# Sheet1.net
KiCad netlist of a schematic drawn in Altium Designer
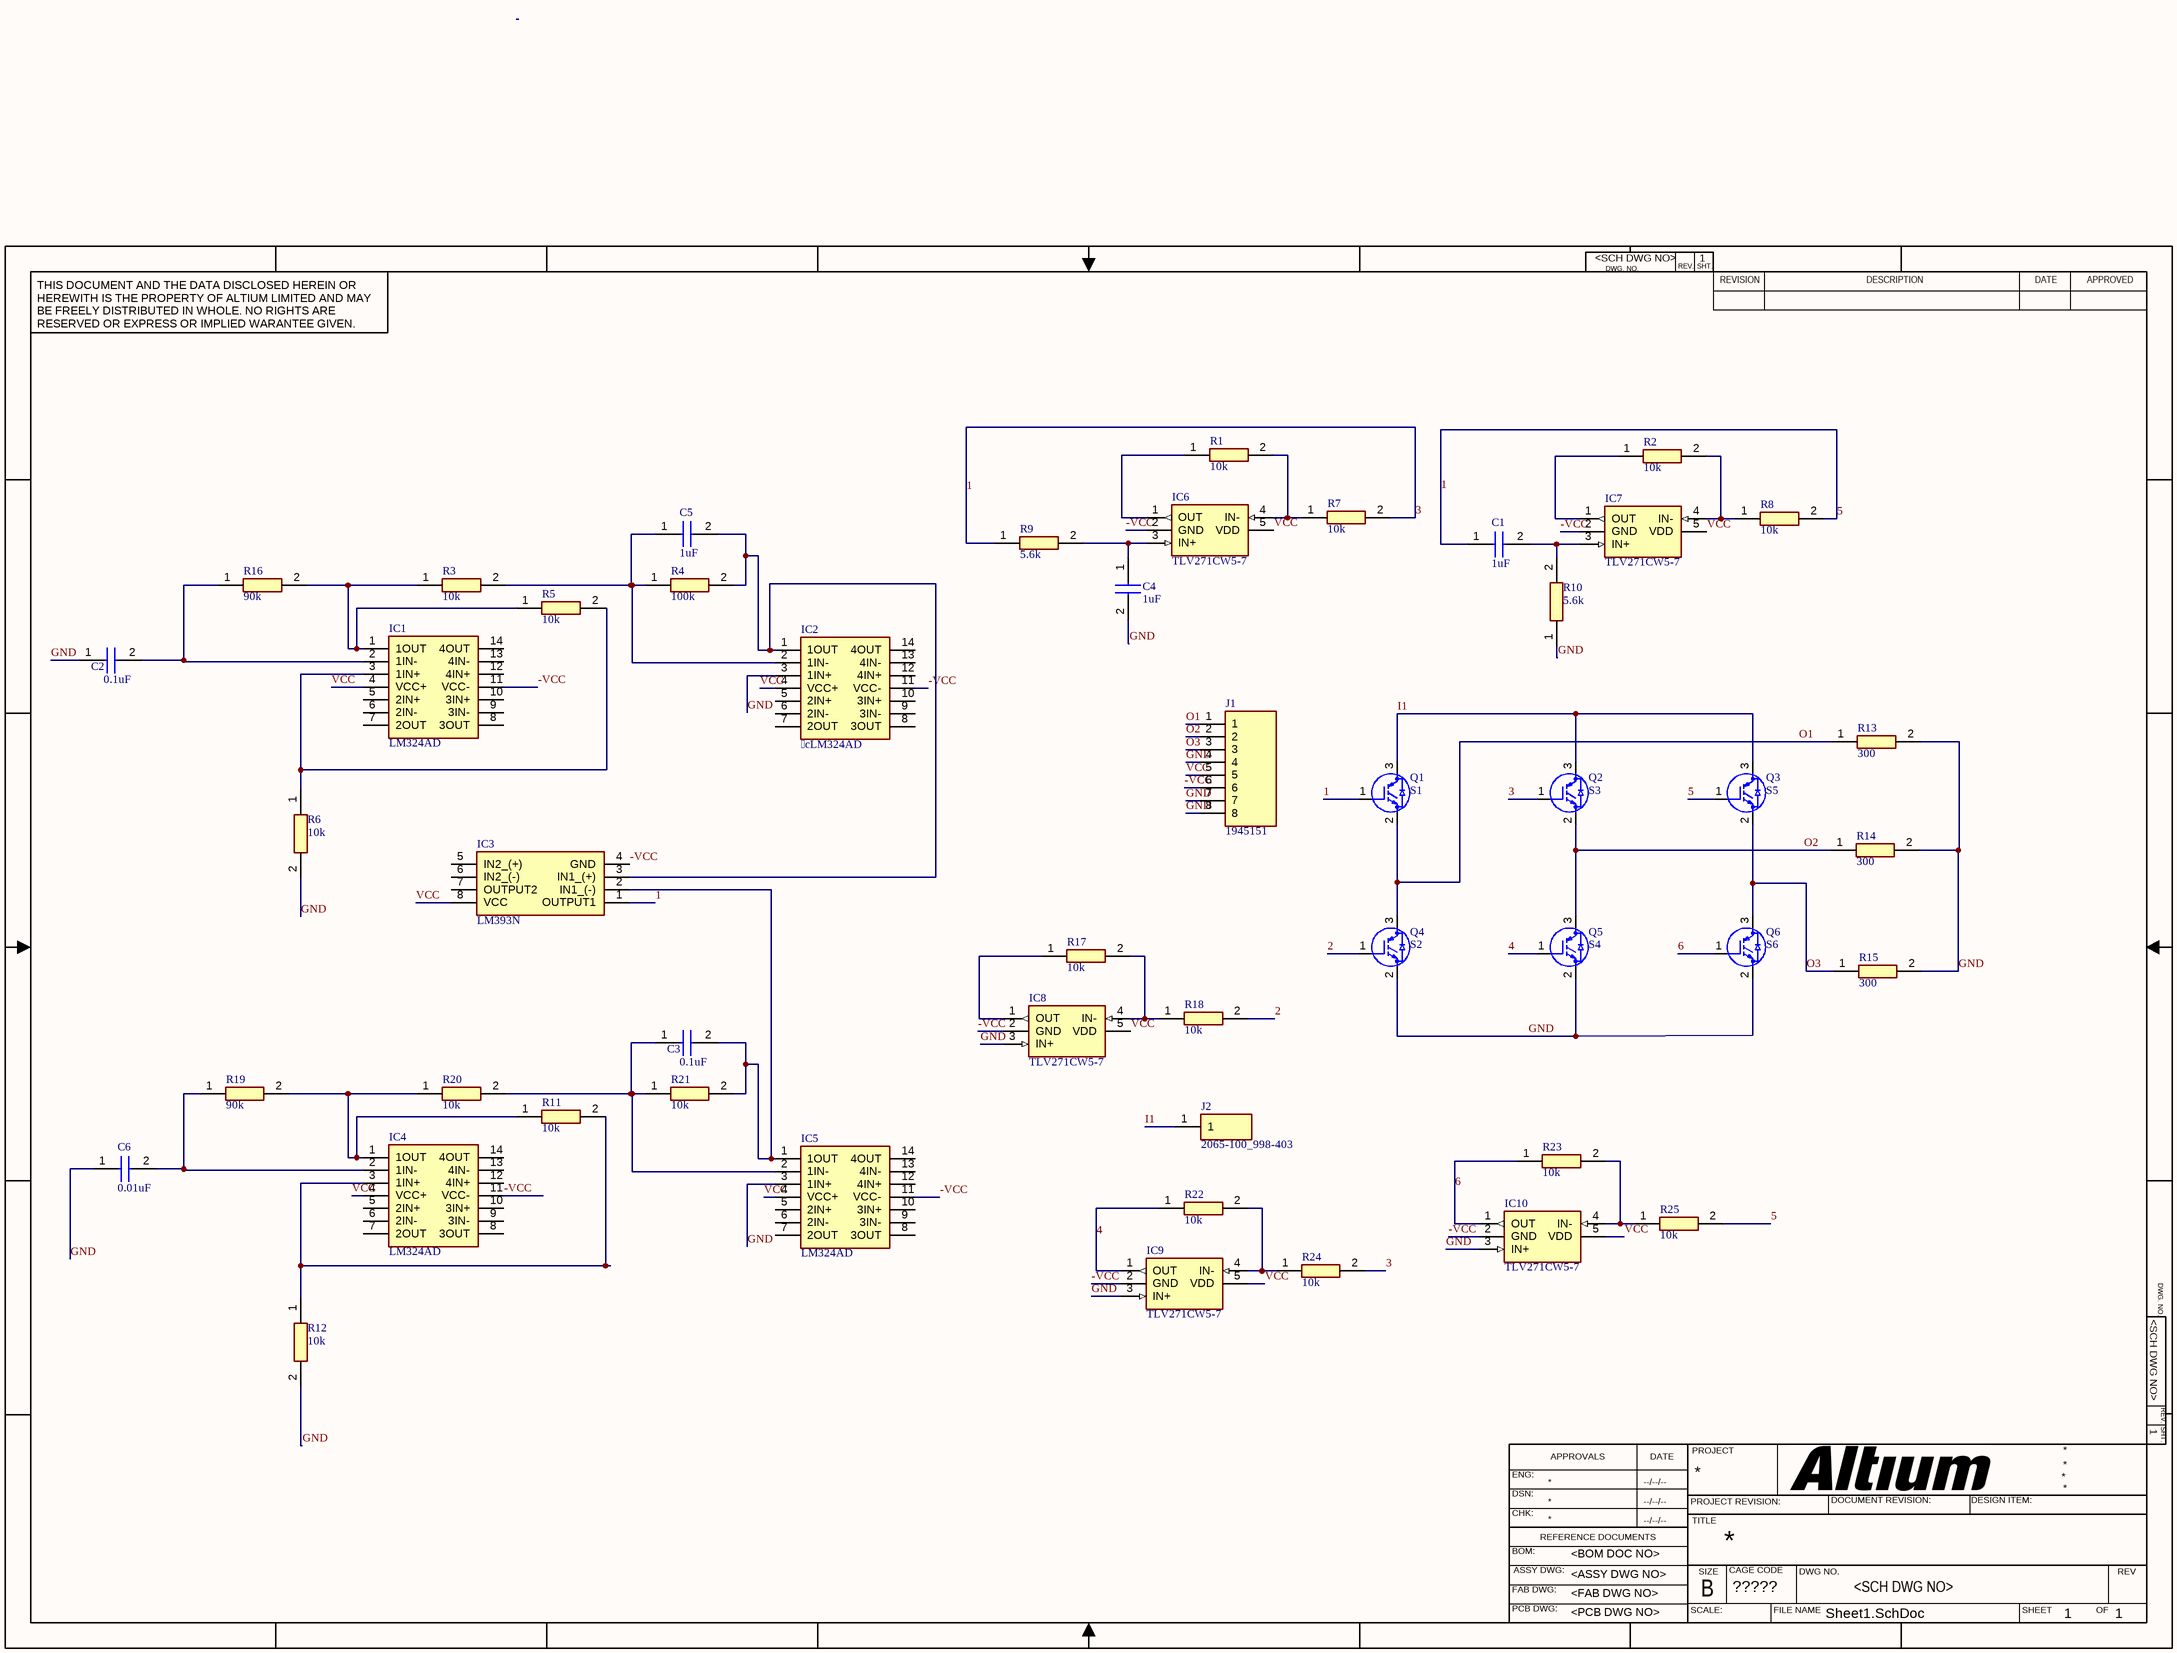
[diagram p0: Sheet1.SchDoc]

(export (version "E")
  (design (tool "Eeschema 10.0.6"))
  (components
    (comp (ref "C1")
      (value "1uF")
      (footprint "PcbLib1:CAPC1005X55N")
      (description "Capacitor")
      (fields
        (field (name "MANUFACTURER_PART_NUMBER") "JMK105BJ105KV-F")
        (field (name "MOUSER PART NUMBER") "963-JMK105BJ105KV-F")
      )
      (libsource (lib "*") (part "JMK105BJ105KV-F"))
    )
    (comp (ref "C2")
      (value "0.1uF")
      (footprint "SamacSys:CAPC1005X55N")
      (description "Capacitor")
      (fields
        (field (name "MANUFACTURER_PART_NUMBER") "CL05B104KP5NNNC")
        (field (name "MOUSER PART NUMBER") "187-CL05B104KP5NNNC")
      )
      (libsource (lib "*") (part "CL05B104KP5NNNC"))
    )
    (comp (ref "C3")
      (value "0.1uF")
      (footprint "SamacSys:CAPC1005X55N")
      (description "Capacitor")
      (fields
        (field (name "MANUFACTURER_PART_NUMBER") "CL05B104KP5NNNC")
        (field (name "MOUSER PART NUMBER") "187-CL05B104KP5NNNC")
      )
      (libsource (lib "*") (part "CL05B104KP5NNNC"))
    )
    (comp (ref "C4")
      (value "1uF")
      (footprint "PcbLib1:CAPC1005X55N")
      (description "Capacitor")
      (fields
        (field (name "MANUFACTURER_PART_NUMBER") "JMK105BJ105KV-F")
        (field (name "MOUSER PART NUMBER") "963-JMK105BJ105KV-F")
      )
      (libsource (lib "*") (part "JMK105BJ105KV-F"))
    )
    (comp (ref "C5")
      (value "1uF")
      (footprint "SamacSys:CAPC1005X55N")
      (description "Capacitor")
      (fields
        (field (name "MANUFACTURER_PART_NUMBER") "JMK105BJ105KV-F")
        (field (name "MOUSER PART NUMBER") "963-JMK105BJ105KV-F")
      )
      (libsource (lib "*") (part "JMK105BJ105KV-F"))
    )
    (comp (ref "C6")
      (value "0.01uF")
      (footprint "SamacSys:C0603")
      (description "Capacitor")
      (fields
        (field (name "MANUFACTURER_PART_NUMBER") "C0603C103J5REC7411")
        (field (name "MOUSER PART NUMBER") "80-C0603C103J5RE7411")
      )
      (libsource (lib "*") (part "C0603C103J5REC7411"))
    )
    (comp (ref "IC1")
      (value "LM324AD")
      (footprint "SamacSys:SOIC127P600X175-14N")
      (description "Integrated Circuit")
      (fields (field (name "MOUSER PART NUMBER") "595-LM324AD"))
      (libsource (lib "*") (part "LM324AD"))
    )
    (comp (ref "IC2")
      (value "cLM324AD")
      (footprint "SamacSys:SOIC127P600X175-14N")
      (description "Integrated Circuit")
      (fields
        (field (name "MANUFACTURER_PART_NUMBER") "LM324AD")
        (field (name "MOUSER PART NUMBER") "595-LM324AD")
      )
      (libsource (lib "*") (part "LM324AD"))
    )
    (comp (ref "IC3")
      (value "LM393N")
      (footprint "SamacSys:DIP762W53P254L980H533Q8N")
      (description "Integrated Circuit")
      (fields (field (name "MOUSER PART NUMBER") "512-LM393N"))
      (libsource (lib "Schlib1") (part "LM393N"))
    )
    (comp (ref "IC4")
      (value "LM324AD")
      (footprint "SamacSys:SOIC127P600X175-14N")
      (description "Integrated Circuit")
      (fields (field (name "MOUSER PART NUMBER") "595-LM324AD"))
      (libsource (lib "*") (part "LM324AD"))
    )
    (comp (ref "IC5")
      (value "LM324AD")
      (footprint "SamacSys:SOIC127P600X175-14N")
      (description "Integrated Circuit")
      (fields (field (name "MOUSER PART NUMBER") "595-LM324AD"))
      (libsource (lib "*") (part "LM324AD"))
    )
    (comp (ref "IC6")
      (value "TLV271CW5-7")
      (footprint "PcbLib1:SOT95P285X130-5N")
      (description "Integrated Circuit")
      (fields (field (name "MOUSER PART NUMBER") "621-TLV271CW5-7"))
      (libsource (lib "*") (part "TLV271CW5-7"))
    )
    (comp (ref "IC7")
      (value "TLV271CW5-7")
      (footprint "PcbLib1:SOT95P285X130-5N")
      (description "Integrated Circuit")
      (fields (field (name "MOUSER PART NUMBER") "621-TLV271CW5-7"))
      (libsource (lib "*") (part "TLV271CW5-7"))
    )
    (comp (ref "IC8")
      (value "TLV271CW5-7")
      (footprint "PcbLib1:SOT95P285X130-5N")
      (description "Integrated Circuit")
      (fields (field (name "MOUSER PART NUMBER") "621-TLV271CW5-7"))
      (libsource (lib "*") (part "TLV271CW5-7"))
    )
    (comp (ref "IC9")
      (value "TLV271CW5-7")
      (footprint "PcbLib1:SOT95P285X130-5N")
      (description "Integrated Circuit")
      (fields (field (name "MOUSER PART NUMBER") "621-TLV271CW5-7"))
      (libsource (lib "*") (part "TLV271CW5-7"))
    )
    (comp (ref "IC10")
      (value "TLV271CW5-7")
      (footprint "PcbLib1:SOT95P285X130-5N")
      (description "Integrated Circuit")
      (fields (field (name "MOUSER PART NUMBER") "621-TLV271CW5-7"))
      (libsource (lib "*") (part "TLV271CW5-7"))
    )
    (comp (ref "J1")
      (value "1945151")
      (footprint "PcbLib1:1945151")
      (description "Connector")
      (fields (field (name "MOUSER PART NUMBER") "651-1945151"))
      (libsource (lib "*") (part "1945151"))
    )
    (comp (ref "J2")
      (value "2065-100_998-403")
      (footprint "PcbLib1:2065100998403")
      (description "Connector")
      (fields (field (name "MANUFACTURER_PART_NUMBER") "2065-100/998-403"))
      (libsource (lib "*") (part "2065-100_998-403"))
    )
    (comp (ref "Q1")
      (value "S1")
      (footprint "SamacSys:TO544P521X1592X2557-3P")
      (description "Transistor IGBT")
      (fields
        (field (name "MANUFACTURER_PART_NUMBER") "IHW30N160R5XKSA1")
        (field (name "MOUSER PART NUMBER") "726-IHW30N160R5XKSA1")
      )
      (libsource (lib "*") (part "IHW30N160R5XKSA1"))
    )
    (comp (ref "Q2")
      (value "S3")
      (footprint "SamacSys:TO544P521X1592X2557-3P")
      (description "Transistor IGBT")
      (fields
        (field (name "MANUFACTURER_PART_NUMBER") "IHW30N160R5XKSA1")
        (field (name "MOUSER PART NUMBER") "726-IHW30N160R5XKSA1")
      )
      (libsource (lib "*") (part "IHW30N160R5XKSA1"))
    )
    (comp (ref "Q3")
      (value "S5")
      (footprint "SamacSys:TO544P521X1592X2557-3P")
      (description "Transistor IGBT")
      (fields
        (field (name "MANUFACTURER_PART_NUMBER") "IHW30N160R5XKSA1")
        (field (name "MOUSER PART NUMBER") "726-IHW30N160R5XKSA1")
      )
      (libsource (lib "*") (part "IHW30N160R5XKSA1"))
    )
    (comp (ref "Q4")
      (value "S2")
      (footprint "SamacSys:TO544P521X1592X2557-3P")
      (description "Transistor IGBT")
      (fields
        (field (name "MANUFACTURER_PART_NUMBER") "IHW30N160R5XKSA1")
        (field (name "MOUSER PART NUMBER") "726-IHW30N160R5XKSA1")
      )
      (libsource (lib "*") (part "IHW30N160R5XKSA1"))
    )
    (comp (ref "Q5")
      (value "S4")
      (footprint "SamacSys:TO544P521X1592X2557-3P")
      (description "Transistor IGBT")
      (fields
        (field (name "MANUFACTURER_PART_NUMBER") "IHW30N160R5XKSA1")
        (field (name "MOUSER PART NUMBER") "726-IHW30N160R5XKSA1")
      )
      (libsource (lib "*") (part "IHW30N160R5XKSA1"))
    )
    (comp (ref "Q6")
      (value "S6")
      (footprint "SamacSys:TO544P521X1592X2557-3P")
      (description "Transistor IGBT")
      (fields
        (field (name "MANUFACTURER_PART_NUMBER") "IHW30N160R5XKSA1")
        (field (name "MOUSER PART NUMBER") "726-IHW30N160R5XKSA1")
      )
      (libsource (lib "*") (part "IHW30N160R5XKSA1"))
    )
    (comp (ref "R1")
      (value "10k")
      (footprint "SamacSys:RESC2012X60N")
      (description "Resistor")
      (fields
        (field (name "MANUFACTURER_PART_NUMBER") "RC0805FR-0710KL")
        (field (name "MOUSER PART NUMBER") "603-RC0805FR-0710KL")
      )
      (libsource (lib "") (part "RC0805FR-0710KL_1"))
    )
    (comp (ref "R2")
      (value "10k")
      (footprint "SamacSys:RESC2012X60N")
      (description "Resistor")
      (fields
        (field (name "MANUFACTURER_PART_NUMBER") "RC0805FR-0710KL")
        (field (name "MOUSER PART NUMBER") "603-RC0805FR-0710KL")
      )
      (libsource (lib "") (part "RC0805FR-0710KL_1"))
    )
    (comp (ref "R3")
      (value "10k")
      (footprint "SamacSys:RESC2012X60N")
      (description "Resistor")
      (fields
        (field (name "MANUFACTURER_PART_NUMBER") "RC0805FR-0710KL")
        (field (name "MOUSER PART NUMBER") "603-RC0805FR-0710KL")
      )
      (libsource (lib "") (part "RC0805FR-0710KL_1"))
    )
    (comp (ref "R4")
      (value "100k")
      (footprint "SamacSys:RESC2012X60N")
      (description "Resistor")
      (fields
        (field (name "MANUFACTURER_PART_NUMBER") "RC0805FR-07100KL")
        (field (name "MOUSER PART NUMBER") "603-RC0805FR-07100KL")
      )
      (libsource (lib "Schlib1") (part "RC0805FR-07100KL"))
    )
    (comp (ref "R5")
      (value "10k")
      (footprint "SamacSys:RESC2012X60N")
      (description "Resistor")
      (fields
        (field (name "MANUFACTURER_PART_NUMBER") "RC0805FR-0710KL")
        (field (name "MOUSER PART NUMBER") "603-RC0805FR-0710KL")
      )
      (libsource (lib "") (part "RC0805FR-0710KL_1"))
    )
    (comp (ref "R6")
      (value "10k")
      (footprint "SamacSys:RESC2012X60N")
      (description "Resistor")
      (fields
        (field (name "MANUFACTURER_PART_NUMBER") "RC0805FR-0710KL")
        (field (name "MOUSER PART NUMBER") "603-RC0805FR-0710KL")
      )
      (libsource (lib "Schlib1") (part "RC0805FR-0710KL"))
    )
    (comp (ref "R7")
      (value "10k")
      (footprint "SamacSys:RESC2012X60N")
      (description "Resistor")
      (fields
        (field (name "MANUFACTURER_PART_NUMBER") "RC0805FR-0710KL")
        (field (name "MOUSER PART NUMBER") "603-RC0805FR-0710KL")
      )
      (libsource (lib "") (part "RC0805FR-0710KL_1"))
    )
    (comp (ref "R8")
      (value "10k")
      (footprint "SamacSys:RESC2012X60N")
      (description "Resistor")
      (fields
        (field (name "MANUFACTURER_PART_NUMBER") "RC0805FR-0710KL")
        (field (name "MOUSER PART NUMBER") "603-RC0805FR-0710KL")
      )
      (libsource (lib "") (part "RC0805FR-0710KL_1"))
    )
    (comp (ref "R9")
      (value "5.6k")
      (footprint "PcbLib1:RESC1005X40N")
      (description "Resistor")
      (fields
        (field (name "MANUFACTURER_PART_NUMBER") "RC0402FR-075K6L")
        (field (name "MOUSER PART NUMBER") "603-RC0402FR-075K6L")
      )
      (libsource (lib "") (part "RC0402FR-075K6L_1"))
    )
    (comp (ref "R10")
      (value "5.6k")
      (footprint "PcbLib1:RESC1005X40N")
      (description "Resistor")
      (fields
        (field (name "MANUFACTURER_PART_NUMBER") "RC0402FR-075K6L")
        (field (name "MOUSER PART NUMBER") "603-RC0402FR-075K6L")
      )
      (libsource (lib "*") (part "RC0402FR-075K6L"))
    )
    (comp (ref "R11")
      (value "10k")
      (footprint "SamacSys:RESC2012X60N")
      (description "Resistor")
      (fields
        (field (name "MANUFACTURER_PART_NUMBER") "RC0805FR-0710KL")
        (field (name "MOUSER PART NUMBER") "603-RC0805FR-0710KL")
      )
      (libsource (lib "") (part "RC0805FR-0710KL_1"))
    )
    (comp (ref "R12")
      (value "10k")
      (footprint "SamacSys:RESC2012X60N")
      (description "Resistor")
      (fields
        (field (name "MANUFACTURER_PART_NUMBER") "RC0805FR-0710KL")
        (field (name "MOUSER PART NUMBER") "603-RC0805FR-0710KL")
      )
      (libsource (lib "Schlib1") (part "RC0805FR-0710KL"))
    )
    (comp (ref "R13")
      (value "300")
      (footprint "SamacSys:RESC1632X65N")
      (description "Resistor")
      (fields
        (field (name "MANUFACTURER_PART_NUMBER") "LTR18EZPJ301")
        (field (name "MOUSER PART NUMBER") "755-LTR18EZPJ301")
      )
      (libsource (lib "*") (part "LTR18EZPJ301"))
    )
    (comp (ref "R14")
      (value "300")
      (footprint "SamacSys:RESC1632X65N")
      (description "Resistor")
      (fields
        (field (name "MANUFACTURER_PART_NUMBER") "LTR18EZPJ301")
        (field (name "MOUSER PART NUMBER") "755-LTR18EZPJ301")
      )
      (libsource (lib "*") (part "LTR18EZPJ301"))
    )
    (comp (ref "R15")
      (value "300")
      (footprint "SamacSys:RESC1632X65N")
      (description "Resistor")
      (fields
        (field (name "MANUFACTURER_PART_NUMBER") "LTR18EZPJ301")
        (field (name "MOUSER PART NUMBER") "755-LTR18EZPJ301")
      )
      (libsource (lib "*") (part "LTR18EZPJ301"))
    )
    (comp (ref "R16")
      (value "90k")
      (footprint "SamacSys:RESC3116X65N")
      (description "Resistor")
      (fields
        (field (name "MANUFACTURER_PART_NUMBER") "RT1206DRE0790KL")
        (field (name "MOUSER PART NUMBER") "603-RT1206DRE0790KL")
      )
      (libsource (lib "*") (part "RT1206DRE0790KL"))
    )
    (comp (ref "R17")
      (value "10k")
      (footprint "SamacSys:RESC2012X60N")
      (description "Resistor")
      (fields
        (field (name "MANUFACTURER_PART_NUMBER") "RC0805FR-0710KL")
        (field (name "MOUSER PART NUMBER") "603-RC0805FR-0710KL")
      )
      (libsource (lib "") (part "RC0805FR-0710KL_1"))
    )
    (comp (ref "R18")
      (value "10k")
      (footprint "SamacSys:RESC2012X60N")
      (description "Resistor")
      (fields
        (field (name "MANUFACTURER_PART_NUMBER") "RC0805FR-0710KL")
        (field (name "MOUSER PART NUMBER") "603-RC0805FR-0710KL")
      )
      (libsource (lib "") (part "RC0805FR-0710KL_1"))
    )
    (comp (ref "R19")
      (value "90k")
      (footprint "SamacSys:RESC3116X65N")
      (description "Resistor")
      (fields
        (field (name "MANUFACTURER_PART_NUMBER") "RT1206DRE0790KL")
        (field (name "MOUSER PART NUMBER") "603-RT1206DRE0790KL")
      )
      (libsource (lib "*") (part "RT1206DRE0790KL"))
    )
    (comp (ref "R20")
      (value "10k")
      (footprint "SamacSys:RESC2012X60N")
      (description "Resistor")
      (fields
        (field (name "MANUFACTURER_PART_NUMBER") "RC0805FR-0710KL")
        (field (name "MOUSER PART NUMBER") "603-RC0805FR-0710KL")
      )
      (libsource (lib "") (part "RC0805FR-0710KL_1"))
    )
    (comp (ref "R21")
      (value "10k")
      (footprint "SamacSys:RESC2012X60N")
      (description "Resistor")
      (fields
        (field (name "MANUFACTURER_PART_NUMBER") "RC0805FR-0710KL")
        (field (name "MOUSER PART NUMBER") "603-RC0805FR-0710KL")
      )
      (libsource (lib "") (part "RC0805FR-0710KL_1"))
    )
    (comp (ref "R22")
      (value "10k")
      (footprint "SamacSys:RESC2012X60N")
      (description "Resistor")
      (fields
        (field (name "MANUFACTURER_PART_NUMBER") "RC0805FR-0710KL")
        (field (name "MOUSER PART NUMBER") "603-RC0805FR-0710KL")
      )
      (libsource (lib "") (part "RC0805FR-0710KL_1"))
    )
    (comp (ref "R23")
      (value "10k")
      (footprint "SamacSys:RESC2012X60N")
      (description "Resistor")
      (fields
        (field (name "MANUFACTURER_PART_NUMBER") "RC0805FR-0710KL")
        (field (name "MOUSER PART NUMBER") "603-RC0805FR-0710KL")
      )
      (libsource (lib "") (part "RC0805FR-0710KL_1"))
    )
    (comp (ref "R24")
      (value "10k")
      (footprint "SamacSys:RESC2012X60N")
      (description "Resistor")
      (fields
        (field (name "MANUFACTURER_PART_NUMBER") "RC0805FR-0710KL")
        (field (name "MOUSER PART NUMBER") "603-RC0805FR-0710KL")
      )
      (libsource (lib "") (part "RC0805FR-0710KL_1"))
    )
    (comp (ref "R25")
      (value "10k")
      (footprint "SamacSys:RESC2012X60N")
      (description "Resistor")
      (fields
        (field (name "MANUFACTURER_PART_NUMBER") "RC0805FR-0710KL")
        (field (name "MOUSER PART NUMBER") "603-RC0805FR-0710KL")
      )
      (libsource (lib "") (part "RC0805FR-0710KL_1"))
    )
  )
  (nets
    (net (code "1") (name "/-VCC") (class "Default")
      (node (ref "IC1") (pin "11") (pinfunction "VCC-_11") (pintype "passive"))
      (node (ref "IC10") (pin "2") (pinfunction "GND_2") (pintype "power_in"))
      (node (ref "IC2") (pin "11") (pinfunction "VCC-_11") (pintype "passive"))
      (node (ref "IC3") (pin "4") (pinfunction "GND_4") (pintype "passive"))
      (node (ref "IC4") (pin "11") (pinfunction "VCC-_11") (pintype "passive"))
      (node (ref "IC5") (pin "11") (pinfunction "VCC-_11") (pintype "passive"))
      (node (ref "IC6") (pin "2") (pinfunction "GND_2") (pintype "power_in"))
      (node (ref "IC7") (pin "2") (pinfunction "GND_2") (pintype "power_in"))
      (node (ref "IC8") (pin "2") (pinfunction "GND_2") (pintype "power_in"))
      (node (ref "IC9") (pin "2") (pinfunction "GND_2") (pintype "power_in"))
      (node (ref "J1") (pin "6") (pinfunction "6_6") (pintype "passive"))
    )
    (net (code "2") (name "/1") (class "Default")
      (node (ref "C1") (pin "1") (pinfunction "1_1") (pintype "passive"))
      (node (ref "IC3") (pin "1") (pinfunction "OUTPUT1_1") (pintype "passive"))
      (node (ref "Q1") (pin "1") (pinfunction "G_1") (pintype "passive"))
      (node (ref "Q2") (pin "1") (pinfunction "G_1") (pintype "passive"))
      (node (ref "Q3") (pin "1") (pinfunction "G_1") (pintype "passive"))
      (node (ref "R24") (pin "2") (pinfunction "2_2") (pintype "passive"))
      (node (ref "R25") (pin "2") (pinfunction "2_2") (pintype "passive"))
      (node (ref "R7") (pin "2") (pinfunction "2_2") (pintype "passive"))
      (node (ref "R8") (pin "2") (pinfunction "2_2") (pintype "passive"))
      (node (ref "R9") (pin "1") (pinfunction "1_1") (pintype "passive"))
    )
    (net (code "3") (name "/2") (class "Default")
      (node (ref "Q4") (pin "1") (pinfunction "G_1") (pintype "passive"))
      (node (ref "R18") (pin "2") (pinfunction "2_2") (pintype "passive"))
    )
    (net (code "4") (name "/4") (class "Default")
      (node (ref "IC9") (pin "1") (pinfunction "OUT_1") (pintype "output"))
      (node (ref "Q5") (pin "1") (pinfunction "G_1") (pintype "passive"))
      (node (ref "R22") (pin "1") (pinfunction "1_1") (pintype "passive"))
    )
    (net (code "5") (name "/6") (class "Default")
      (node (ref "IC10") (pin "1") (pinfunction "OUT_1") (pintype "output"))
      (node (ref "Q6") (pin "1") (pinfunction "G_1") (pintype "passive"))
      (node (ref "R23") (pin "1") (pinfunction "1_1") (pintype "passive"))
    )
    (net (code "6") (name "/GND") (class "Default")
      (node (ref "C2") (pin "1") (pinfunction "1_1") (pintype "passive"))
      (node (ref "C4") (pin "2") (pinfunction "2_2") (pintype "passive"))
      (node (ref "C6") (pin "1") (pinfunction "1_1") (pintype "passive"))
      (node (ref "IC10") (pin "3") (pinfunction "IN+_3") (pintype "input"))
      (node (ref "IC2") (pin "3") (pinfunction "1IN+_3") (pintype "passive"))
      (node (ref "IC5") (pin "3") (pinfunction "1IN+_3") (pintype "passive"))
      (node (ref "IC8") (pin "3") (pinfunction "IN+_3") (pintype "input"))
      (node (ref "IC9") (pin "3") (pinfunction "IN+_3") (pintype "input"))
      (node (ref "J1") (pin "4") (pinfunction "4_4") (pintype "passive"))
      (node (ref "J1") (pin "7") (pinfunction "7_7") (pintype "passive"))
      (node (ref "J1") (pin "8") (pinfunction "8_8") (pintype "passive"))
      (node (ref "Q4") (pin "2") (pinfunction "E_2") (pintype "passive"))
      (node (ref "Q5") (pin "2") (pinfunction "E_2") (pintype "passive"))
      (node (ref "Q6") (pin "2") (pinfunction "E_2") (pintype "passive"))
      (node (ref "R10") (pin "1") (pinfunction "1_1") (pintype "passive"))
      (node (ref "R12") (pin "2") (pinfunction "2_2") (pintype "passive"))
      (node (ref "R13") (pin "2") (pinfunction "2_2") (pintype "passive"))
      (node (ref "R14") (pin "2") (pinfunction "2_2") (pintype "passive"))
      (node (ref "R15") (pin "2") (pinfunction "2_2") (pintype "passive"))
      (node (ref "R6") (pin "2") (pinfunction "2_2") (pintype "passive"))
    )
    (net (code "7") (name "/I1") (class "Default")
      (node (ref "J2") (pin "1") (pinfunction "1_1") (pintype "passive"))
      (node (ref "Q1") (pin "3") (pinfunction "C_3") (pintype "passive"))
      (node (ref "Q2") (pin "3") (pinfunction "C_3") (pintype "passive"))
      (node (ref "Q3") (pin "3") (pinfunction "C_3") (pintype "passive"))
    )
    (net (code "8") (name "/O1") (class "Default")
      (node (ref "J1") (pin "1") (pinfunction "1_1") (pintype "passive"))
      (node (ref "Q1") (pin "2") (pinfunction "E_2") (pintype "passive"))
      (node (ref "Q4") (pin "3") (pinfunction "C_3") (pintype "passive"))
      (node (ref "R13") (pin "1") (pinfunction "1_1") (pintype "passive"))
    )
    (net (code "9") (name "/O2") (class "Default")
      (node (ref "J1") (pin "2") (pinfunction "2_2") (pintype "passive"))
      (node (ref "Q2") (pin "2") (pinfunction "E_2") (pintype "passive"))
      (node (ref "Q5") (pin "3") (pinfunction "C_3") (pintype "passive"))
      (node (ref "R14") (pin "1") (pinfunction "1_1") (pintype "passive"))
    )
    (net (code "10") (name "/O3") (class "Default")
      (node (ref "J1") (pin "3") (pinfunction "3_3") (pintype "passive"))
      (node (ref "Q3") (pin "2") (pinfunction "E_2") (pintype "passive"))
      (node (ref "Q6") (pin "3") (pinfunction "C_3") (pintype "passive"))
      (node (ref "R15") (pin "1") (pinfunction "1_1") (pintype "passive"))
    )
    (net (code "11") (name "/VCC") (class "Default")
      (node (ref "IC1") (pin "4") (pinfunction "VCC+_4") (pintype "passive"))
      (node (ref "IC10") (pin "5") (pinfunction "VDD_5") (pintype "power_in"))
      (node (ref "IC2") (pin "4") (pinfunction "VCC+_4") (pintype "passive"))
      (node (ref "IC3") (pin "8") (pinfunction "VCC_8") (pintype "passive"))
      (node (ref "IC4") (pin "4") (pinfunction "VCC+_4") (pintype "passive"))
      (node (ref "IC5") (pin "4") (pinfunction "VCC+_4") (pintype "passive"))
      (node (ref "IC6") (pin "5") (pinfunction "VDD_5") (pintype "power_in"))
      (node (ref "IC7") (pin "5") (pinfunction "VDD_5") (pintype "power_in"))
      (node (ref "IC8") (pin "5") (pinfunction "VDD_5") (pintype "power_in"))
      (node (ref "IC9") (pin "5") (pinfunction "VDD_5") (pintype "power_in"))
      (node (ref "J1") (pin "5") (pinfunction "5_5") (pintype "passive"))
    )
    (net (code "12") (name "Net-(IC1-1IN+)") (class "Default")
      (node (ref "IC1") (pin "3") (pinfunction "1IN+_3") (pintype "passive"))
      (node (ref "R5") (pin "2") (pinfunction "2_2") (pintype "passive"))
      (node (ref "R6") (pin "1") (pinfunction "1_1") (pintype "passive"))
    )
    (net (code "13") (name "Net-(IC1-1IN-)") (class "Default")
      (node (ref "C2") (pin "2") (pinfunction "2_2") (pintype "passive"))
      (node (ref "IC1") (pin "2") (pinfunction "1IN-_2") (pintype "passive"))
      (node (ref "R16") (pin "1") (pinfunction "1_1") (pintype "passive"))
    )
    (net (code "14") (name "Net-(IC1-1OUT)") (class "Default")
      (node (ref "IC1") (pin "1") (pinfunction "1OUT_1") (pintype "passive"))
      (node (ref "R16") (pin "2") (pinfunction "2_2") (pintype "passive"))
      (node (ref "R3") (pin "1") (pinfunction "1_1") (pintype "passive"))
      (node (ref "R5") (pin "1") (pinfunction "1_1") (pintype "passive"))
    )
    (net (code "15") (name "Net-(IC2-1IN-)") (class "Default")
      (node (ref "C5") (pin "1") (pinfunction "1_1") (pintype "passive"))
      (node (ref "IC2") (pin "2") (pinfunction "1IN-_2") (pintype "passive"))
      (node (ref "R3") (pin "2") (pinfunction "2_2") (pintype "passive"))
      (node (ref "R4") (pin "1") (pinfunction "1_1") (pintype "passive"))
    )
    (net (code "16") (name "Net-(IC2-1OUT)") (class "Default")
      (node (ref "C5") (pin "2") (pinfunction "2_2") (pintype "passive"))
      (node (ref "IC2") (pin "1") (pinfunction "1OUT_1") (pintype "passive"))
      (node (ref "IC3") (pin "3") (pinfunction "IN1_(+)_3") (pintype "passive"))
      (node (ref "R4") (pin "2") (pinfunction "2_2") (pintype "passive"))
    )
    (net (code "17") (name "Net-(IC3-IN1_(-))") (class "Default")
      (node (ref "C3") (pin "2") (pinfunction "2_2") (pintype "passive"))
      (node (ref "IC3") (pin "2") (pinfunction "IN1_(-)_2") (pintype "passive"))
      (node (ref "IC5") (pin "1") (pinfunction "1OUT_1") (pintype "passive"))
      (node (ref "R21") (pin "2") (pinfunction "2_2") (pintype "passive"))
    )
    (net (code "18") (name "Net-(IC4-1IN+)") (class "Default")
      (node (ref "IC4") (pin "3") (pinfunction "1IN+_3") (pintype "passive"))
      (node (ref "R11") (pin "2") (pinfunction "2_2") (pintype "passive"))
      (node (ref "R12") (pin "1") (pinfunction "1_1") (pintype "passive"))
    )
    (net (code "19") (name "Net-(IC4-1IN-)") (class "Default")
      (node (ref "C6") (pin "2") (pinfunction "2_2") (pintype "passive"))
      (node (ref "IC4") (pin "2") (pinfunction "1IN-_2") (pintype "passive"))
      (node (ref "R19") (pin "1") (pinfunction "1_1") (pintype "passive"))
    )
    (net (code "20") (name "Net-(IC4-1OUT)") (class "Default")
      (node (ref "IC4") (pin "1") (pinfunction "1OUT_1") (pintype "passive"))
      (node (ref "R11") (pin "1") (pinfunction "1_1") (pintype "passive"))
      (node (ref "R19") (pin "2") (pinfunction "2_2") (pintype "passive"))
      (node (ref "R20") (pin "1") (pinfunction "1_1") (pintype "passive"))
    )
    (net (code "21") (name "Net-(IC5-1IN-)") (class "Default")
      (node (ref "C3") (pin "1") (pinfunction "1_1") (pintype "passive"))
      (node (ref "IC5") (pin "2") (pinfunction "1IN-_2") (pintype "passive"))
      (node (ref "R20") (pin "2") (pinfunction "2_2") (pintype "passive"))
      (node (ref "R21") (pin "1") (pinfunction "1_1") (pintype "passive"))
    )
    (net (code "22") (name "Net-(IC6-IN+)") (class "Default")
      (node (ref "C4") (pin "1") (pinfunction "1_1") (pintype "passive"))
      (node (ref "IC6") (pin "3") (pinfunction "IN+_3") (pintype "input"))
      (node (ref "R9") (pin "2") (pinfunction "2_2") (pintype "passive"))
    )
    (net (code "23") (name "Net-(IC6-IN-)") (class "Default")
      (node (ref "IC6") (pin "4") (pinfunction "IN-_4") (pintype "input"))
      (node (ref "R1") (pin "2") (pinfunction "2_2") (pintype "passive"))
      (node (ref "R7") (pin "1") (pinfunction "1_1") (pintype "passive"))
    )
    (net (code "24") (name "Net-(IC6-OUT)") (class "Default")
      (node (ref "IC6") (pin "1") (pinfunction "OUT_1") (pintype "output"))
      (node (ref "R1") (pin "1") (pinfunction "1_1") (pintype "passive"))
    )
    (net (code "25") (name "Net-(IC7-IN+)") (class "Default")
      (node (ref "C1") (pin "2") (pinfunction "2_2") (pintype "passive"))
      (node (ref "IC7") (pin "3") (pinfunction "IN+_3") (pintype "input"))
      (node (ref "R10") (pin "2") (pinfunction "2_2") (pintype "passive"))
    )
    (net (code "26") (name "Net-(IC7-IN-)") (class "Default")
      (node (ref "IC7") (pin "4") (pinfunction "IN-_4") (pintype "input"))
      (node (ref "R2") (pin "2") (pinfunction "2_2") (pintype "passive"))
      (node (ref "R8") (pin "1") (pinfunction "1_1") (pintype "passive"))
    )
    (net (code "27") (name "Net-(IC7-OUT)") (class "Default")
      (node (ref "IC7") (pin "1") (pinfunction "OUT_1") (pintype "output"))
      (node (ref "R2") (pin "1") (pinfunction "1_1") (pintype "passive"))
    )
    (net (code "28") (name "Net-(IC8-IN-)") (class "Default")
      (node (ref "IC8") (pin "4") (pinfunction "IN-_4") (pintype "input"))
      (node (ref "R17") (pin "2") (pinfunction "2_2") (pintype "passive"))
      (node (ref "R18") (pin "1") (pinfunction "1_1") (pintype "passive"))
    )
    (net (code "29") (name "Net-(IC8-OUT)") (class "Default")
      (node (ref "IC8") (pin "1") (pinfunction "OUT_1") (pintype "output"))
      (node (ref "R17") (pin "1") (pinfunction "1_1") (pintype "passive"))
    )
    (net (code "30") (name "Net-(IC9-IN-)") (class "Default")
      (node (ref "IC9") (pin "4") (pinfunction "IN-_4") (pintype "input"))
      (node (ref "R22") (pin "2") (pinfunction "2_2") (pintype "passive"))
      (node (ref "R24") (pin "1") (pinfunction "1_1") (pintype "passive"))
    )
    (net (code "31") (name "Net-(IC10-IN-)") (class "Default")
      (node (ref "IC10") (pin "4") (pinfunction "IN-_4") (pintype "input"))
      (node (ref "R23") (pin "2") (pinfunction "2_2") (pintype "passive"))
      (node (ref "R25") (pin "1") (pinfunction "1_1") (pintype "passive"))
    )
    (net (code "32") (name "unconnected-(IC1-2IN+-Pad5)") (class "Default")
      (node (ref "IC1") (pin "5") (pinfunction "2IN+_5") (pintype "passive"))
    )
    (net (code "33") (name "unconnected-(IC1-2IN--Pad6)") (class "Default")
      (node (ref "IC1") (pin "6") (pinfunction "2IN-_6") (pintype "passive"))
    )
    (net (code "34") (name "unconnected-(IC1-2OUT-Pad7)") (class "Default")
      (node (ref "IC1") (pin "7") (pinfunction "2OUT_7") (pintype "passive"))
    )
    (net (code "35") (name "unconnected-(IC1-3IN+-Pad10)") (class "Default")
      (node (ref "IC1") (pin "10") (pinfunction "3IN+_10") (pintype "passive"))
    )
    (net (code "36") (name "unconnected-(IC1-3IN--Pad9)") (class "Default")
      (node (ref "IC1") (pin "9") (pinfunction "3IN-_9") (pintype "passive"))
    )
    (net (code "37") (name "unconnected-(IC1-3OUT-Pad8)") (class "Default")
      (node (ref "IC1") (pin "8") (pinfunction "3OUT_8") (pintype "passive"))
    )
    (net (code "38") (name "unconnected-(IC1-4IN+-Pad12)") (class "Default")
      (node (ref "IC1") (pin "12") (pinfunction "4IN+_12") (pintype "passive"))
    )
    (net (code "39") (name "unconnected-(IC1-4IN--Pad13)") (class "Default")
      (node (ref "IC1") (pin "13") (pinfunction "4IN-_13") (pintype "passive"))
    )
    (net (code "40") (name "unconnected-(IC1-4OUT-Pad14)") (class "Default")
      (node (ref "IC1") (pin "14") (pinfunction "4OUT_14") (pintype "passive"))
    )
    (net (code "41") (name "unconnected-(IC2-2IN+-Pad5)") (class "Default")
      (node (ref "IC2") (pin "5") (pinfunction "2IN+_5") (pintype "passive"))
    )
    (net (code "42") (name "unconnected-(IC2-2IN--Pad6)") (class "Default")
      (node (ref "IC2") (pin "6") (pinfunction "2IN-_6") (pintype "passive"))
    )
    (net (code "43") (name "unconnected-(IC2-2OUT-Pad7)") (class "Default")
      (node (ref "IC2") (pin "7") (pinfunction "2OUT_7") (pintype "passive"))
    )
    (net (code "44") (name "unconnected-(IC2-3IN+-Pad10)") (class "Default")
      (node (ref "IC2") (pin "10") (pinfunction "3IN+_10") (pintype "passive"))
    )
    (net (code "45") (name "unconnected-(IC2-3IN--Pad9)") (class "Default")
      (node (ref "IC2") (pin "9") (pinfunction "3IN-_9") (pintype "passive"))
    )
    (net (code "46") (name "unconnected-(IC2-3OUT-Pad8)") (class "Default")
      (node (ref "IC2") (pin "8") (pinfunction "3OUT_8") (pintype "passive"))
    )
    (net (code "47") (name "unconnected-(IC2-4IN+-Pad12)") (class "Default")
      (node (ref "IC2") (pin "12") (pinfunction "4IN+_12") (pintype "passive"))
    )
    (net (code "48") (name "unconnected-(IC2-4IN--Pad13)") (class "Default")
      (node (ref "IC2") (pin "13") (pinfunction "4IN-_13") (pintype "passive"))
    )
    (net (code "49") (name "unconnected-(IC2-4OUT-Pad14)") (class "Default")
      (node (ref "IC2") (pin "14") (pinfunction "4OUT_14") (pintype "passive"))
    )
    (net (code "50") (name "unconnected-(IC3-IN2_(+)-Pad5)") (class "Default")
      (node (ref "IC3") (pin "5") (pinfunction "IN2_(+)_5") (pintype "passive"))
    )
    (net (code "51") (name "unconnected-(IC3-IN2_(-)-Pad6)") (class "Default")
      (node (ref "IC3") (pin "6") (pinfunction "IN2_(-)_6") (pintype "passive"))
    )
    (net (code "52") (name "unconnected-(IC3-OUTPUT2-Pad7)") (class "Default")
      (node (ref "IC3") (pin "7") (pinfunction "OUTPUT2_7") (pintype "passive"))
    )
    (net (code "53") (name "unconnected-(IC4-2IN+-Pad5)") (class "Default")
      (node (ref "IC4") (pin "5") (pinfunction "2IN+_5") (pintype "passive"))
    )
    (net (code "54") (name "unconnected-(IC4-2IN--Pad6)") (class "Default")
      (node (ref "IC4") (pin "6") (pinfunction "2IN-_6") (pintype "passive"))
    )
    (net (code "55") (name "unconnected-(IC4-2OUT-Pad7)") (class "Default")
      (node (ref "IC4") (pin "7") (pinfunction "2OUT_7") (pintype "passive"))
    )
    (net (code "56") (name "unconnected-(IC4-3IN+-Pad10)") (class "Default")
      (node (ref "IC4") (pin "10") (pinfunction "3IN+_10") (pintype "passive"))
    )
    (net (code "57") (name "unconnected-(IC4-3IN--Pad9)") (class "Default")
      (node (ref "IC4") (pin "9") (pinfunction "3IN-_9") (pintype "passive"))
    )
    (net (code "58") (name "unconnected-(IC4-3OUT-Pad8)") (class "Default")
      (node (ref "IC4") (pin "8") (pinfunction "3OUT_8") (pintype "passive"))
    )
    (net (code "59") (name "unconnected-(IC4-4IN+-Pad12)") (class "Default")
      (node (ref "IC4") (pin "12") (pinfunction "4IN+_12") (pintype "passive"))
    )
    (net (code "60") (name "unconnected-(IC4-4IN--Pad13)") (class "Default")
      (node (ref "IC4") (pin "13") (pinfunction "4IN-_13") (pintype "passive"))
    )
    (net (code "61") (name "unconnected-(IC4-4OUT-Pad14)") (class "Default")
      (node (ref "IC4") (pin "14") (pinfunction "4OUT_14") (pintype "passive"))
    )
    (net (code "62") (name "unconnected-(IC5-2IN+-Pad5)") (class "Default")
      (node (ref "IC5") (pin "5") (pinfunction "2IN+_5") (pintype "passive"))
    )
    (net (code "63") (name "unconnected-(IC5-2IN--Pad6)") (class "Default")
      (node (ref "IC5") (pin "6") (pinfunction "2IN-_6") (pintype "passive"))
    )
    (net (code "64") (name "unconnected-(IC5-2OUT-Pad7)") (class "Default")
      (node (ref "IC5") (pin "7") (pinfunction "2OUT_7") (pintype "passive"))
    )
    (net (code "65") (name "unconnected-(IC5-3IN+-Pad10)") (class "Default")
      (node (ref "IC5") (pin "10") (pinfunction "3IN+_10") (pintype "passive"))
    )
    (net (code "66") (name "unconnected-(IC5-3IN--Pad9)") (class "Default")
      (node (ref "IC5") (pin "9") (pinfunction "3IN-_9") (pintype "passive"))
    )
    (net (code "67") (name "unconnected-(IC5-3OUT-Pad8)") (class "Default")
      (node (ref "IC5") (pin "8") (pinfunction "3OUT_8") (pintype "passive"))
    )
    (net (code "68") (name "unconnected-(IC5-4IN+-Pad12)") (class "Default")
      (node (ref "IC5") (pin "12") (pinfunction "4IN+_12") (pintype "passive"))
    )
    (net (code "69") (name "unconnected-(IC5-4IN--Pad13)") (class "Default")
      (node (ref "IC5") (pin "13") (pinfunction "4IN-_13") (pintype "passive"))
    )
    (net (code "70") (name "unconnected-(IC5-4OUT-Pad14)") (class "Default")
      (node (ref "IC5") (pin "14") (pinfunction "4OUT_14") (pintype "passive"))
    )
  )
)
